# SL_R_Overcurrent_Analog.net
KiCad netlist of a schematic drawn in EAGLE
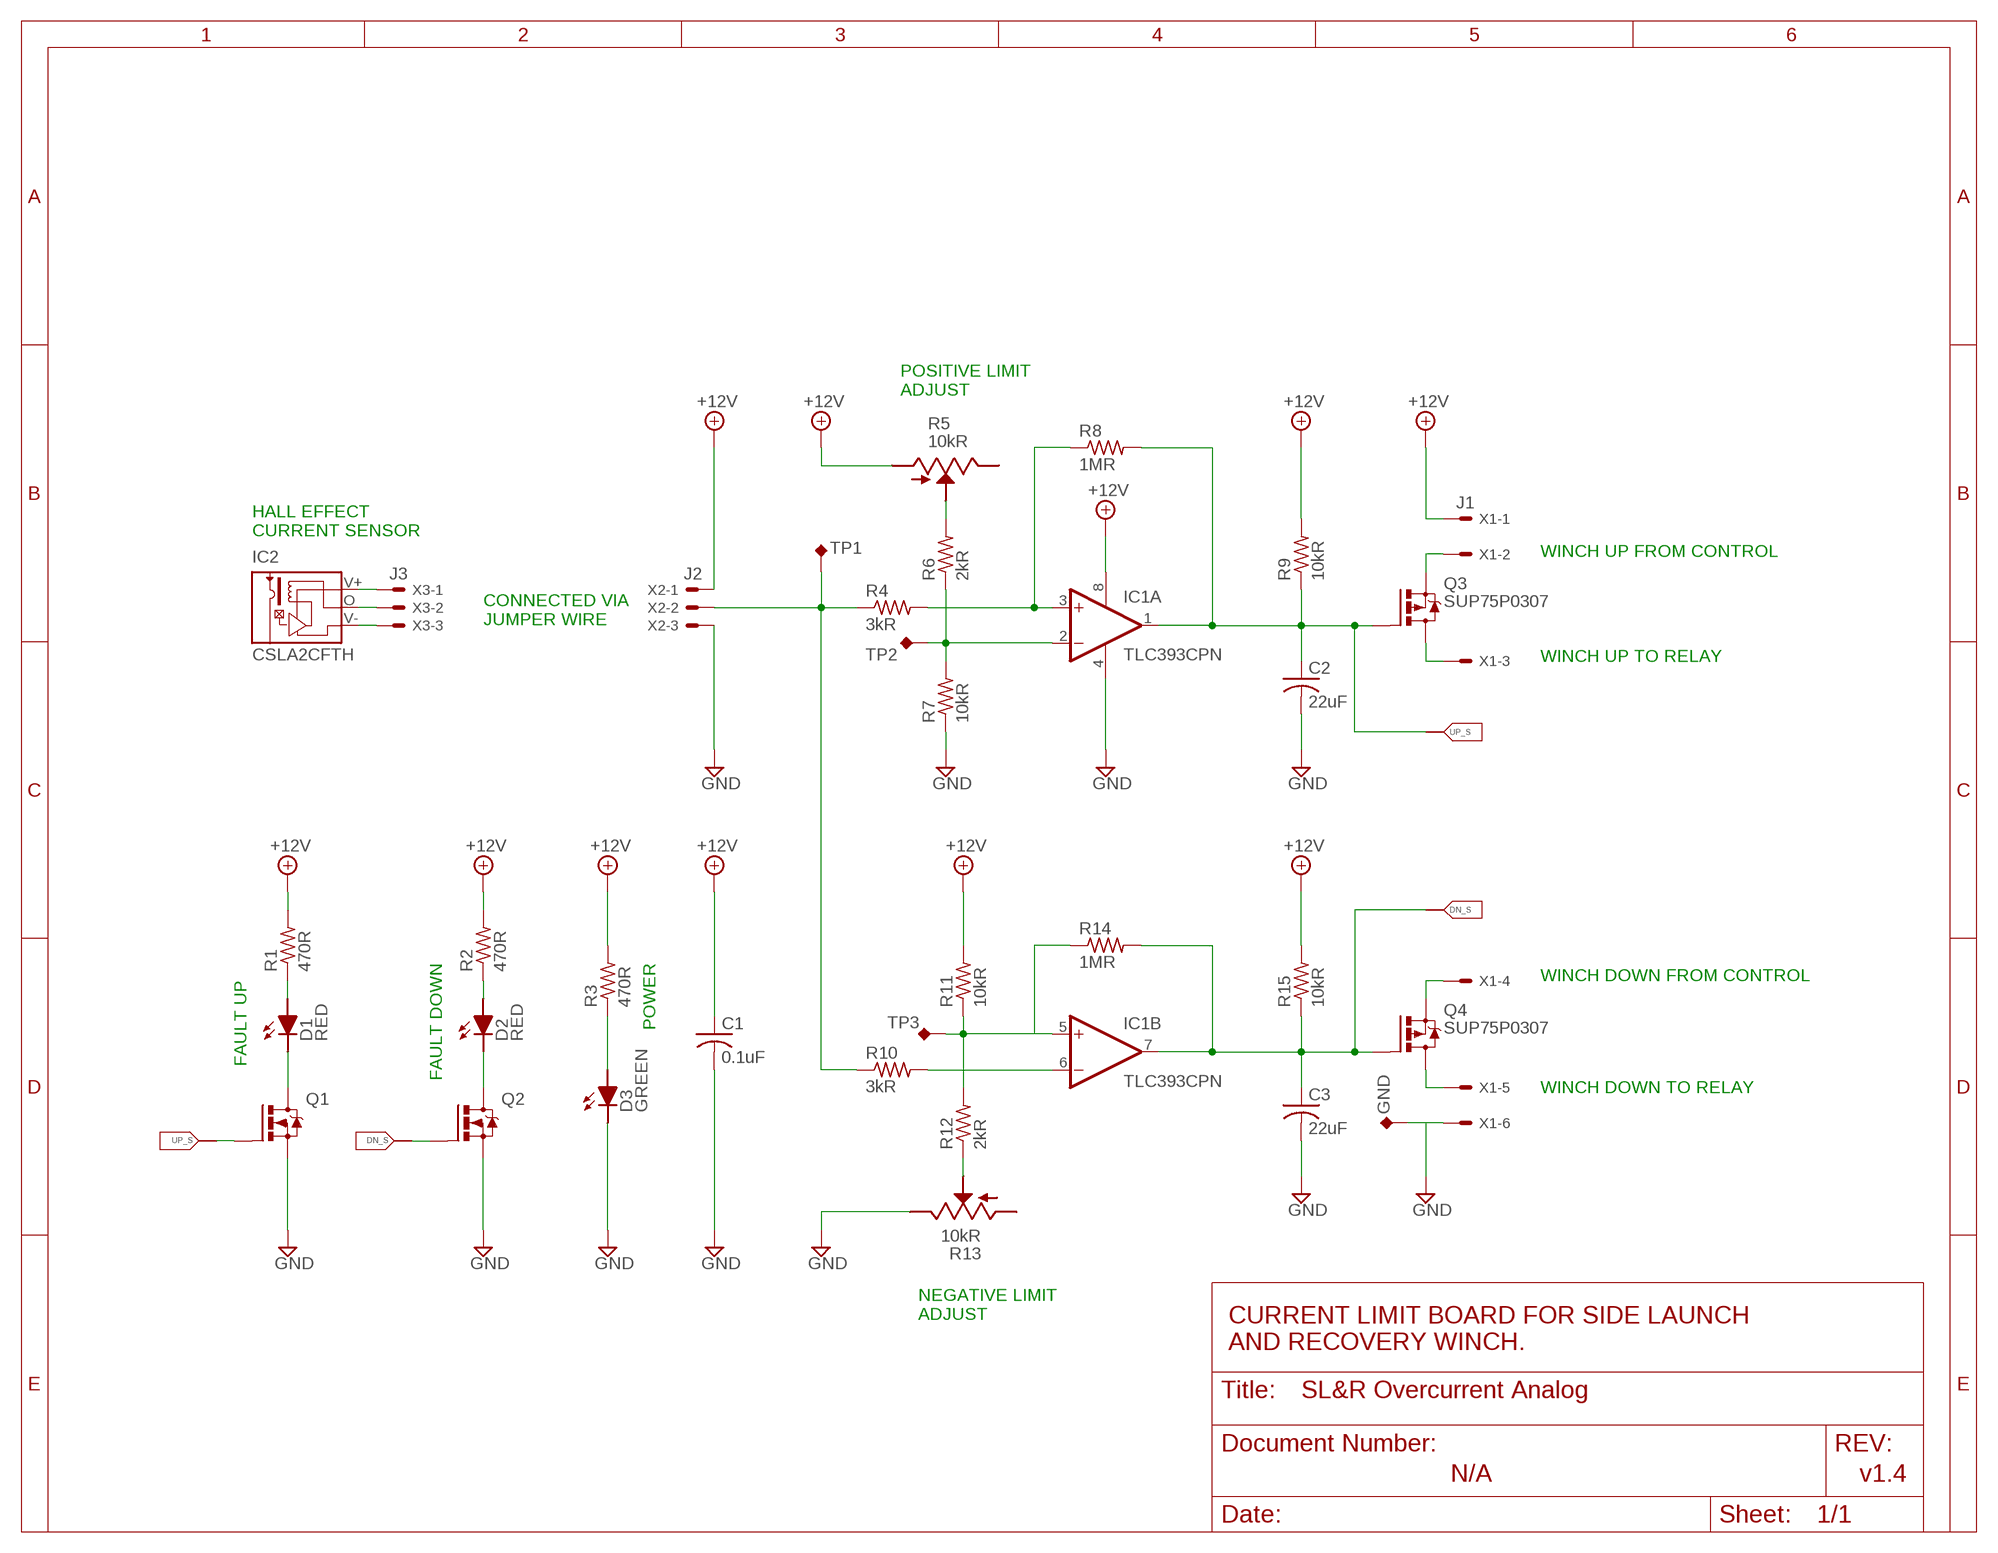
[diagram p0: schematic, sheet 1]

(export (version "E")
  (design (tool "Eeschema 10.0.6"))
  (components
    (comp (ref "C1")
      (value "0.1uF")
      (footprint "eagle-import:C050-024X044")
      (libsource (lib "eagle-import") (part "CAPACITOR-US"))
    )
    (comp (ref "C2")
      (value "22uF")
      (footprint "eagle-import:C025-050X050")
      (libsource (lib "eagle-import") (part "CAPACITOR-US025-050X050"))
    )
    (comp (ref "C3")
      (value "22uF")
      (footprint "eagle-import:C025-050X050")
      (libsource (lib "eagle-import") (part "CAPACITOR-US025-050X050"))
    )
    (comp (ref "D1")
      (value "RED")
      (footprint "eagle-import:LED5MM")
      (libsource (lib "eagle-import") (part "LED"))
    )
    (comp (ref "D2")
      (value "RED")
      (footprint "eagle-import:LED5MM")
      (libsource (lib "eagle-import") (part "LED"))
    )
    (comp (ref "D3")
      (value "GREEN")
      (footprint "eagle-import:LED5MM")
      (libsource (lib "eagle-import") (part "LED"))
    )
    (comp (ref "FRAME1")
      (value "FRAME_A_L")
      (footprint "eagle-import:FRAME_A_L")
      (libsource (lib "eagle-import") (part "FRAME_A_L"))
    )
    (comp (ref "GND")
      (value "TEST_POINT")
      (footprint "eagle-import:TESTLOOP")
      (libsource (lib "eagle-import") (part "TEST_POINT"))
    )
    (comp (ref "IC1")
      (value "TLC393CPN")
      (footprint "eagle-import:DIL08")
      (libsource (lib "eagle-import") (part "TLC393CPN"))
    )
    (comp (ref "IC2")
      (value "CSLA2CFTH")
      (footprint "eagle-import:CSLA2CF")
      (libsource (lib "eagle-import") (part "CSLA2CFTH"))
    )
    (comp (ref "Q1")
      (value "2N7000")
      (footprint "eagle-import:TO92-")
      (libsource (lib "eagle-import") (part "2N7000"))
    )
    (comp (ref "Q2")
      (value "2N7000")
      (footprint "eagle-import:TO92-")
      (libsource (lib "eagle-import") (part "2N7000"))
    )
    (comp (ref "Q3")
      (value "SUP75P0307")
      (footprint "eagle-import:TO220BV")
      (libsource (lib "eagle-import") (part "SUP75P0307"))
    )
    (comp (ref "Q4")
      (value "SUP75P0307")
      (footprint "eagle-import:TO220BV")
      (libsource (lib "eagle-import") (part "SUP75P0307"))
    )
    (comp (ref "R1")
      (value "470R")
      (footprint "eagle-import:0204_7")
      (libsource (lib "eagle-import") (part "SL&R Overcurrent Analog_RESISTOR-US0204/7"))
    )
    (comp (ref "R2")
      (value "470R")
      (footprint "eagle-import:0204_7")
      (libsource (lib "eagle-import") (part "SL&R Overcurrent Analog_RESISTOR-US0204/7"))
    )
    (comp (ref "R3")
      (value "470R")
      (footprint "eagle-import:0204_7")
      (libsource (lib "eagle-import") (part "SL&R Overcurrent Analog_RESISTOR-US0204/7"))
    )
    (comp (ref "R4")
      (value "3kR")
      (footprint "eagle-import:0204_7")
      (libsource (lib "eagle-import") (part "RESISTOR-US0204/7"))
    )
    (comp (ref "R5")
      (value "10kR")
      (footprint "eagle-import:RTRIM3296W")
      (libsource (lib "eagle-import") (part "POT"))
    )
    (comp (ref "R6")
      (value "2kR")
      (footprint "eagle-import:0204_7")
      (libsource (lib "eagle-import") (part "RESISTOR-US0204/7"))
    )
    (comp (ref "R7")
      (value "10kR")
      (footprint "eagle-import:0204_7")
      (libsource (lib "eagle-import") (part "RESISTOR-US0204/7"))
    )
    (comp (ref "R8")
      (value "1MR")
      (footprint "eagle-import:0204_7")
      (libsource (lib "eagle-import") (part "RESISTOR-US0204/7"))
    )
    (comp (ref "R9")
      (value "10kR")
      (footprint "eagle-import:0204_7")
      (libsource (lib "eagle-import") (part "RESISTOR-US0204/7"))
    )
    (comp (ref "R10")
      (value "3kR")
      (footprint "eagle-import:0204_7")
      (libsource (lib "eagle-import") (part "RESISTOR-US0204/7"))
    )
    (comp (ref "R11")
      (value "10kR")
      (footprint "eagle-import:0204_7")
      (libsource (lib "eagle-import") (part "RESISTOR-US0204/7"))
    )
    (comp (ref "R12")
      (value "2kR")
      (footprint "eagle-import:0204_7")
      (libsource (lib "eagle-import") (part "RESISTOR-US0204/7"))
    )
    (comp (ref "R13")
      (value "10kR")
      (footprint "eagle-import:RTRIM3296W")
      (libsource (lib "eagle-import") (part "POT"))
    )
    (comp (ref "R14")
      (value "1MR")
      (footprint "eagle-import:0204_7")
      (libsource (lib "eagle-import") (part "RESISTOR-US0204/7"))
    )
    (comp (ref "R15")
      (value "10kR")
      (footprint "eagle-import:0204_7")
      (libsource (lib "eagle-import") (part "RESISTOR-US0204/7"))
    )
    (comp (ref "TP1")
      (value "TEST_POINT")
      (footprint "eagle-import:TESTLOOP")
      (libsource (lib "eagle-import") (part "TEST_POINT"))
    )
    (comp (ref "TP2")
      (value "TEST_POINT")
      (footprint "eagle-import:TESTLOOP")
      (libsource (lib "eagle-import") (part "TEST_POINT"))
    )
    (comp (ref "TP3")
      (value "TEST_POINT")
      (footprint "eagle-import:TESTLOOP")
      (libsource (lib "eagle-import") (part "TEST_POINT"))
    )
    (comp (ref "U$1")
      (value "DOCFIELD")
      (footprint "eagle-import:DOCFIELD")
      (libsource (lib "eagle-import") (part "DOCFIELD"))
    )
    (comp (ref "X1")
      (value "J1")
      (footprint "eagle-import:22-23-2061")
      (fields (field (name "MF") "MOLEX") (field (name "MPN") "22-23-2061"))
      (libsource (lib "eagle-import") (part "6PIN_HEADER"))
    )
    (comp (ref "X2")
      (value "J2")
      (footprint "eagle-import:22-23-2031")
      (fields (field (name "MF") "MOLEX") (field (name "MPN") "22-23-2031"))
      (libsource (lib "eagle-import") (part "22-23-2031"))
    )
    (comp (ref "X3")
      (value "J3")
      (footprint "eagle-import:22-23-2031")
      (fields (field (name "MF") "MOLEX") (field (name "MPN") "22-23-2031"))
      (libsource (lib "eagle-import") (part "22-23-2031"))
    )
  )
  (nets
    (net (code "1") (name "+12V") (class "Default")
      (node (ref "C1") (pin "1") (pinfunction "1_1") (pintype "passive"))
      (node (ref "IC1") (pin "8") (pinfunction "V+_8") (pintype "power_in"))
      (node (ref "R1") (pin "2") (pinfunction "2_2") (pintype "passive"))
      (node (ref "R11") (pin "2") (pinfunction "2_2") (pintype "passive"))
      (node (ref "R15") (pin "2") (pinfunction "2_2") (pintype "passive"))
      (node (ref "R2") (pin "2") (pinfunction "2_2") (pintype "passive"))
      (node (ref "R3") (pin "2") (pinfunction "2_2") (pintype "passive"))
      (node (ref "R5") (pin "3") (pinfunction "3_3") (pintype "passive"))
      (node (ref "R9") (pin "2") (pinfunction "2_2") (pintype "passive"))
      (node (ref "X1") (pin "1") (pinfunction "S_1") (pintype "passive"))
      (node (ref "X2") (pin "1") (pinfunction "S_1") (pintype "passive"))
    )
    (net (code "2") (name "/N$6") (class "Default")
      (node (ref "C2") (pin "1") (pinfunction "1_1") (pintype "passive"))
      (node (ref "IC1") (pin "1") (pinfunction "OUT_1") (pintype "output"))
      (node (ref "Q1") (pin "2") (pinfunction "G_2") (pintype "passive"))
      (node (ref "Q3") (pin "G") (pinfunction "G_G") (pintype "passive"))
      (node (ref "R8") (pin "2") (pinfunction "2_2") (pintype "passive"))
      (node (ref "R9") (pin "1") (pinfunction "1_1") (pintype "passive"))
    )
    (net (code "3") (name "/N$7") (class "Default")
      (node (ref "C3") (pin "1") (pinfunction "1_1") (pintype "passive"))
      (node (ref "IC1") (pin "7") (pinfunction "OUT_7") (pintype "output"))
      (node (ref "Q2") (pin "2") (pinfunction "G_2") (pintype "passive"))
      (node (ref "Q4") (pin "G") (pinfunction "G_G") (pintype "passive"))
      (node (ref "R14") (pin "2") (pinfunction "2_2") (pintype "passive"))
      (node (ref "R15") (pin "1") (pinfunction "1_1") (pintype "passive"))
    )
    (net (code "4") (name "GND") (class "Default")
      (node (ref "C1") (pin "2") (pinfunction "2_2") (pintype "passive"))
      (node (ref "C2") (pin "2") (pinfunction "2_2") (pintype "passive"))
      (node (ref "C3") (pin "2") (pinfunction "2_2") (pintype "passive"))
      (node (ref "D3") (pin "K") (pinfunction "C_K") (pintype "passive"))
      (node (ref "GND") (pin "P$1") (pinfunction "TP_P$1") (pintype "input"))
      (node (ref "IC1") (pin "4") (pinfunction "V-_4") (pintype "power_in"))
      (node (ref "Q1") (pin "3") (pinfunction "S_3") (pintype "passive"))
      (node (ref "Q2") (pin "3") (pinfunction "S_3") (pintype "passive"))
      (node (ref "R13") (pin "1") (pinfunction "1_1") (pintype "passive"))
      (node (ref "R7") (pin "1") (pinfunction "1_1") (pintype "passive"))
      (node (ref "X1") (pin "6") (pinfunction "S_6") (pintype "passive"))
      (node (ref "X2") (pin "3") (pinfunction "S_3") (pintype "passive"))
    )
    (net (code "5") (name "Net-(D1-C)") (class "Default")
      (node (ref "D1") (pin "K") (pinfunction "C_K") (pintype "passive"))
      (node (ref "Q1") (pin "1") (pinfunction "D_1") (pintype "passive"))
    )
    (net (code "6") (name "Net-(D1-PadA)") (class "Default")
      (node (ref "D1") (pin "A") (pinfunction "A_A") (pintype "passive"))
      (node (ref "R1") (pin "1") (pinfunction "1_1") (pintype "passive"))
    )
    (net (code "7") (name "Net-(D2-C)") (class "Default")
      (node (ref "D2") (pin "K") (pinfunction "C_K") (pintype "passive"))
      (node (ref "Q2") (pin "1") (pinfunction "D_1") (pintype "passive"))
    )
    (net (code "8") (name "Net-(D2-PadA)") (class "Default")
      (node (ref "D2") (pin "A") (pinfunction "A_A") (pintype "passive"))
      (node (ref "R2") (pin "1") (pinfunction "1_1") (pintype "passive"))
    )
    (net (code "9") (name "Net-(D3-PadA)") (class "Default")
      (node (ref "D3") (pin "A") (pinfunction "A_A") (pintype "passive"))
      (node (ref "R3") (pin "1") (pinfunction "1_1") (pintype "passive"))
    )
    (net (code "10") (name "Net-(IC1A-+IN)") (class "Default")
      (node (ref "IC1") (pin "3") (pinfunction "+IN_3") (pintype "input"))
      (node (ref "R4") (pin "2") (pinfunction "2_2") (pintype "passive"))
      (node (ref "R8") (pin "1") (pinfunction "1_1") (pintype "passive"))
    )
    (net (code "11") (name "Net-(IC1A--IN)") (class "Default")
      (node (ref "IC1") (pin "2") (pinfunction "-IN_2") (pintype "input"))
      (node (ref "R6") (pin "1") (pinfunction "1_1") (pintype "passive"))
      (node (ref "R7") (pin "2") (pinfunction "2_2") (pintype "passive"))
      (node (ref "TP2") (pin "P$1") (pinfunction "TP_P$1") (pintype "input"))
    )
    (net (code "12") (name "Net-(IC1B-+IN)") (class "Default")
      (node (ref "IC1") (pin "5") (pinfunction "+IN_5") (pintype "input"))
      (node (ref "R11") (pin "1") (pinfunction "1_1") (pintype "passive"))
      (node (ref "R12") (pin "2") (pinfunction "2_2") (pintype "passive"))
      (node (ref "R14") (pin "1") (pinfunction "1_1") (pintype "passive"))
      (node (ref "TP3") (pin "P$1") (pinfunction "TP_P$1") (pintype "input"))
    )
    (net (code "13") (name "Net-(IC1B--IN)") (class "Default")
      (node (ref "IC1") (pin "6") (pinfunction "-IN_6") (pintype "input"))
      (node (ref "R10") (pin "2") (pinfunction "2_2") (pintype "passive"))
    )
    (net (code "14") (name "Net-(IC2-M)") (class "Default")
      (node (ref "IC2") (pin "O") (pinfunction "M_O") (pintype "output"))
      (node (ref "X3") (pin "2") (pinfunction "S_2") (pintype "passive"))
    )
    (net (code "15") (name "Net-(R5-Pad2)") (class "Default")
      (node (ref "R5") (pin "2") (pinfunction "2_2") (pintype "passive"))
      (node (ref "R6") (pin "2") (pinfunction "2_2") (pintype "passive"))
    )
    (net (code "16") (name "Net-(R12-Pad1)") (class "Default")
      (node (ref "R12") (pin "1") (pinfunction "1_1") (pintype "passive"))
      (node (ref "R13") (pin "2") (pinfunction "2_2") (pintype "passive"))
    )
    (net (code "17") (name "Net-(TP1-TP)") (class "Default")
      (node (ref "R10") (pin "1") (pinfunction "1_1") (pintype "passive"))
      (node (ref "R4") (pin "1") (pinfunction "1_1") (pintype "passive"))
      (node (ref "TP1") (pin "P$1") (pinfunction "TP_P$1") (pintype "input"))
      (node (ref "X2") (pin "2") (pinfunction "S_2") (pintype "passive"))
    )
    (net (code "18") (name "Net-(X1B-S)") (class "Default")
      (node (ref "Q3") (pin "S") (pinfunction "S_S") (pintype "passive"))
      (node (ref "X1") (pin "2") (pinfunction "S_2") (pintype "passive"))
    )
    (net (code "19") (name "Net-(X1C-S)") (class "Default")
      (node (ref "Q3") (pin "D") (pinfunction "D_D") (pintype "passive"))
      (node (ref "X1") (pin "3") (pinfunction "S_3") (pintype "passive"))
    )
    (net (code "20") (name "Net-(X1D-S)") (class "Default")
      (node (ref "Q4") (pin "S") (pinfunction "S_S") (pintype "passive"))
      (node (ref "X1") (pin "4") (pinfunction "S_4") (pintype "passive"))
    )
    (net (code "21") (name "Net-(X1E-S)") (class "Default")
      (node (ref "Q4") (pin "D") (pinfunction "D_D") (pintype "passive"))
      (node (ref "X1") (pin "5") (pinfunction "S_5") (pintype "passive"))
    )
    (net (code "22") (name "Net-(X3A-S)") (class "Default")
      (node (ref "IC2") (pin "V+") (pinfunction "V+_V+") (pintype "input"))
      (node (ref "X3") (pin "1") (pinfunction "S_1") (pintype "passive"))
    )
    (net (code "23") (name "Net-(X3C-S)") (class "Default")
      (node (ref "IC2") (pin "V-") (pinfunction "V-_V-") (pintype "input"))
      (node (ref "X3") (pin "3") (pinfunction "S_3") (pintype "passive"))
    )
    (net (code "24") (name "unconnected-(R5-Pad1)") (class "Default")
      (node (ref "R5") (pin "1") (pinfunction "1_1") (pintype "passive"))
    )
    (net (code "25") (name "unconnected-(R13-Pad3)") (class "Default")
      (node (ref "R13") (pin "3") (pinfunction "3_3") (pintype "passive"))
    )
  )
)
